# LDO.net
KiCad netlist of a schematic drawn in Altium Designer
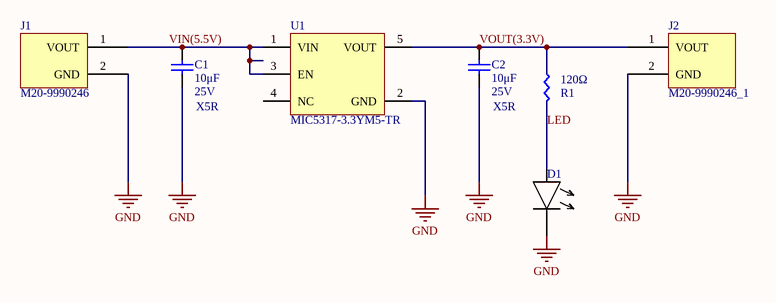
[diagram p0: LDO.SchDoc]

(export (version "E")
  (design (tool "Eeschema 10.0.6"))
  (components
    (comp (ref "C1")
      (value "10μF")
      (footprint "CAP0805")
      (description "CAP CER 1UF 25V X7R 0805")
      (fields
        (field (name "VOLTAGE RATING") "25V")
        (field (name "CLASS") "X5R")
        (field (name "Comment") "GCM21BR71E105KA56L")
      )
      (libsource (lib "Bootcamp_Schematic_Library") (part "GCM21BR71E105KA56L"))
    )
    (comp (ref "C2")
      (value "10μF")
      (footprint "CAP0805")
      (description "CAP CER 1UF 25V X7R 0805")
      (fields
        (field (name "VOLTAGE RATING") "25V")
        (field (name "CLASS") "X5R")
        (field (name "Comment") "GCM21BR71E105KA56L")
      )
      (libsource (lib "Bootcamp_Schematic_Library") (part "GCM21BR71E105KA56L"))
    )
    (comp (ref "D1")
      (value "~")
      (footprint "FP-LTST-C170GKT-MFG")
      (description "LED GREEN CLEAR SMD")
      (fields (field (name "MANFACTURER PART NUMBER") "LTST-C170GKT"))
      (libsource (lib "Bootcamp_Schematic_Library") (part "LTST-C170GKT"))
    )
    (comp (ref "J1")
      (value "M20-9990246")
      (footprint "FP-M20-9990246-MFG - duplicate")
      (description "CONN HEADER VERT 2POS 2.54MM")
      (fields (field (name "MANUFACTURER") "Harwin Inc."))
      (libsource (lib "Bootcamp_Schematic_Library") (part "M20-9990246"))
    )
    (comp (ref "J2")
      (value "M20-9990246_1")
      (footprint "FP-M20-9990246-MFG - duplicate")
      (description "CONN HEADER VERT 2POS 2.54MM")
      (fields
        (field (name "MANUFACTURER") "Harwin Inc.")
        (field (name "MANUFACTURER PART NUMBER") "M20-9990246")
      )
      (libsource (lib "Bootcamp_Schematic_Library") (part "M20-9990246_1"))
    )
    (comp (ref "R1")
      (value "120Ω")
      (footprint "RES0603")
      (description "RES 10K OHM 1% 1/8W 0603")
      (fields (field (name "Comment") "RNCP0603FTD10K0"))
      (libsource (lib "Bootcamp_Schematic_Library") (part "RNCP0603FTD10K0"))
    )
    (comp (ref "U1")
      (value "MIC5317-3.3YM5-TR")
      (footprint "SOT95P245X145-5N")
      (description "C REG LINEAR 3.3V 150MA SOT23-5")
      (fields (field (name "MANUFACTURER") "Microchip Technology"))
      (libsource (lib "Bootcamp_Schematic_Library") (part "MIC5317-3.3YM5-TR"))
    )
  )
  (nets
    (net (code "2") (name "/VIN(5.5V)") (class "Default")
      (node (ref "C1") (pin "2") (pinfunction "2_2") (pintype "passive"))
      (node (ref "J1") (pin "1") (pinfunction "VOUT_1") (pintype "passive"))
      (node (ref "U1") (pin "1") (pinfunction "VIN_1") (pintype "passive"))
      (node (ref "U1") (pin "3") (pinfunction "EN_3") (pintype "passive"))
    )
    (net (code "3") (name "/VOUT(3.3V)") (class "Default")
      (node (ref "C2") (pin "2") (pinfunction "2_2") (pintype "passive"))
      (node (ref "J2") (pin "1") (pinfunction "VOUT_1") (pintype "passive"))
      (node (ref "U1") (pin "5") (pinfunction "VOUT_5") (pintype "passive"))
    )
    (net (code "4") (name "GND") (class "Default")
      (node (ref "C1") (pin "1") (pinfunction "1_1") (pintype "passive"))
      (node (ref "C2") (pin "1") (pinfunction "1_1") (pintype "passive"))
      (node (ref "J1") (pin "2") (pinfunction "GND_2") (pintype "passive"))
      (node (ref "J2") (pin "2") (pinfunction "GND_2") (pintype "passive"))
      (node (ref "U1") (pin "2") (pinfunction "GND_2") (pintype "passive"))
    )
    (net (code "5") (name "unconnected-(U1-NC-Pad4)") (class "Default")
      (node (ref "U1") (pin "4") (pinfunction "NC_4") (pintype "passive"))
    )
  )
)
